# line_follower.net
KiCad netlist of a schematic drawn in EAGLE
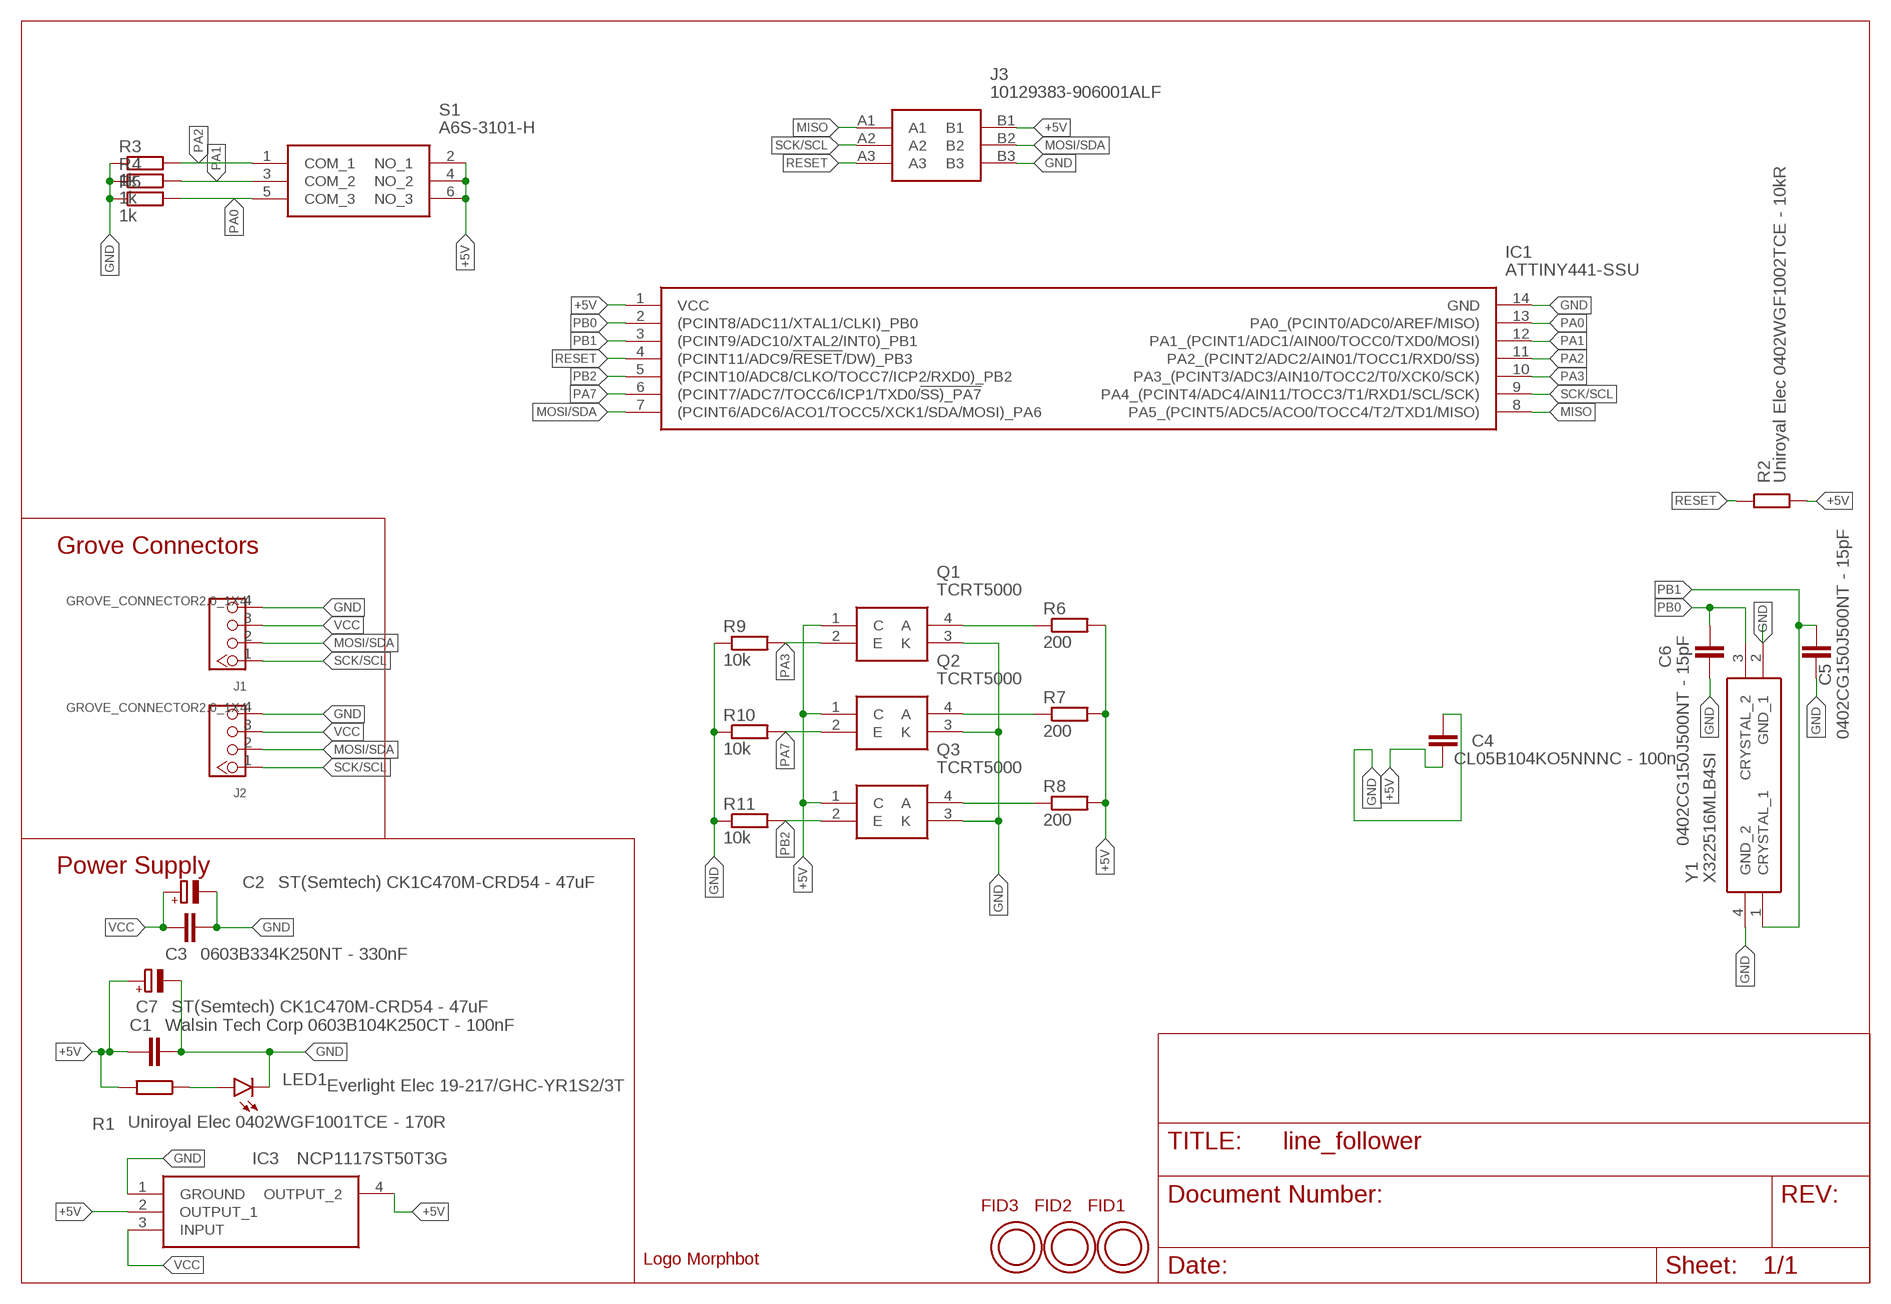
[diagram p0: schematic, sheet 1]

(export (version "E")
  (design (tool "Eeschema 10.0.6"))
  (components
    (comp (ref "C1")
      (value "Walsin Tech Corp 0603B104K250CT - 100nF")
      (footprint "eagle-import:C0603")
      (libsource (lib "eagle-import") (part "C-EUC0603"))
    )
    (comp (ref "C2")
      (value "ST(Semtech) CK1C470M-CRD54 - 47uF")
      (footprint "eagle-import:PANASONIC_C")
      (libsource (lib "eagle-import") (part "CPOL-EUC"))
    )
    (comp (ref "C3")
      (value "0603B334K250NT - 330nF")
      (footprint "eagle-import:C0603")
      (libsource (lib "eagle-import") (part "C-EUC0603"))
    )
    (comp (ref "C4")
      (value "CL05B104KO5NNNC - 100n")
      (footprint "eagle-import:C0402")
      (libsource (lib "eagle-import") (part "C-EUC0402"))
    )
    (comp (ref "C5")
      (value "0402CG150J500NT - 15pF")
      (footprint "eagle-import:C0402")
      (libsource (lib "eagle-import") (part "C-EUC0402"))
    )
    (comp (ref "C6")
      (value "0402CG150J500NT - 15pF")
      (footprint "eagle-import:C0402")
      (libsource (lib "eagle-import") (part "C-EUC0402"))
    )
    (comp (ref "C7")
      (value "ST(Semtech) CK1C470M-CRD54 - 47uF")
      (footprint "eagle-import:PANASONIC_C")
      (libsource (lib "eagle-import") (part "CPOL-EUC"))
    )
    (comp (ref "FID1")
      (value "OPEN-PNP-FIDUCIAL")
      (footprint "eagle-import:OPEN-PNP-FIDUCIAL")
      (libsource (lib "eagle-import") (part "OPEN-PNP-FIDUCIAL"))
    )
    (comp (ref "FID2")
      (value "OPEN-PNP-FIDUCIAL")
      (footprint "eagle-import:OPEN-PNP-FIDUCIAL")
      (libsource (lib "eagle-import") (part "OPEN-PNP-FIDUCIAL"))
    )
    (comp (ref "FID3")
      (value "OPEN-PNP-FIDUCIAL")
      (footprint "eagle-import:OPEN-PNP-FIDUCIAL")
      (libsource (lib "eagle-import") (part "OPEN-PNP-FIDUCIAL"))
    )
    (comp (ref "IC1")
      (value "ATTINY441-SSU")
      (footprint "eagle-import:SOIC127P600X175-14N")
      (fields (field (name "MOUSER_PART_NUMBER") "556-ATTINY441-SSU"))
      (libsource (lib "eagle-import") (part "ATTINY441-SSU"))
    )
    (comp (ref "IC3")
      (value "NCP1117ST50T3G")
      (footprint "eagle-import:SOT230P700X180-4N")
      (fields (field (name "MOUSER_PART_NUMBER") "863-NCP1117ST50T3G"))
      (libsource (lib "eagle-import") (part "NCP1117ST50T3G"))
    )
    (comp (ref "J1")
      (value "GROVE_CONNECTOR2.0_1X4")
      (footprint "eagle-import:2.0_1X4_STRAIGHT")
      (libsource (lib "eagle-import") (part "GROVE_CONNECTOR2.0_1X4"))
    )
    (comp (ref "J2")
      (value "GROVE_CONNECTOR2.0_1X4")
      (footprint "eagle-import:2.0_1X4_STRAIGHT")
      (libsource (lib "eagle-import") (part "GROVE_CONNECTOR2.0_1X4"))
    )
    (comp (ref "J3")
      (value "10129383-906001ALF")
      (footprint "eagle-import:10129383906001ALF")
      (fields (field (name "MOUSER_PART_NUMBER") "649-1012938390601ALF"))
      (libsource (lib "eagle-import") (part "10129383-906001ALF"))
    )
    (comp (ref "LED1")
      (value "Everlight Elec 19-217/GHC-YR1S2/3T")
      (footprint "eagle-import:CHIPLED_0603")
      (libsource (lib "eagle-import") (part "LEDCHIPLED_0603"))
    )
    (comp (ref "Q1")
      (value "TCRT5000")
      (footprint "eagle-import:TCRT5000")
      (fields (field (name "MOUSER_PART_NUMBER") "782-TCRT5000"))
      (libsource (lib "eagle-import") (part "TCRT5000"))
    )
    (comp (ref "Q2")
      (value "TCRT5000")
      (footprint "eagle-import:TCRT5000")
      (fields (field (name "MOUSER_PART_NUMBER") "782-TCRT5000"))
      (libsource (lib "eagle-import") (part "TCRT5000"))
    )
    (comp (ref "Q3")
      (value "TCRT5000")
      (footprint "eagle-import:TCRT5000")
      (fields (field (name "MOUSER_PART_NUMBER") "782-TCRT5000"))
      (libsource (lib "eagle-import") (part "TCRT5000"))
    )
    (comp (ref "R1")
      (value "Uniroyal Elec 0402WGF1001TCE - 170R")
      (footprint "eagle-import:R0402")
      (libsource (lib "eagle-import") (part "R-EU_R0402"))
    )
    (comp (ref "R2")
      (value "Uniroyal Elec 0402WGF1002TCE - 10kR")
      (footprint "eagle-import:R0402")
      (libsource (lib "eagle-import") (part "R-EU_R0402"))
    )
    (comp (ref "R3")
      (value "1k")
      (footprint "eagle-import:R0402")
      (libsource (lib "eagle-import") (part "R-EU_R0402"))
    )
    (comp (ref "R4")
      (value "1k")
      (footprint "eagle-import:R0402")
      (libsource (lib "eagle-import") (part "R-EU_R0402"))
    )
    (comp (ref "R5")
      (value "1k")
      (footprint "eagle-import:R0402")
      (libsource (lib "eagle-import") (part "R-EU_R0402"))
    )
    (comp (ref "R6")
      (value "200")
      (footprint "eagle-import:R0402")
      (libsource (lib "eagle-import") (part "R-EU_R0402"))
    )
    (comp (ref "R7")
      (value "200")
      (footprint "eagle-import:R0402")
      (libsource (lib "eagle-import") (part "R-EU_R0402"))
    )
    (comp (ref "R8")
      (value "200")
      (footprint "eagle-import:R0402")
      (libsource (lib "eagle-import") (part "R-EU_R0402"))
    )
    (comp (ref "R9")
      (value "10k")
      (footprint "eagle-import:R0402")
      (libsource (lib "eagle-import") (part "R-EU_R0402"))
    )
    (comp (ref "R10")
      (value "10k")
      (footprint "eagle-import:R0402")
      (libsource (lib "eagle-import") (part "R-EU_R0402"))
    )
    (comp (ref "R11")
      (value "10k")
      (footprint "eagle-import:R0402")
      (libsource (lib "eagle-import") (part "R-EU_R0402"))
    )
    (comp (ref "S1")
      (value "A6S-3101-H")
      (footprint "eagle-import:A6S3104H")
      (fields (field (name "MOUSER_PART_NUMBER") "653-A6S-3101-H"))
      (libsource (lib "eagle-import") (part "A6S-3101-H"))
    )
    (comp (ref "U$1")
      (value "LOGO_MORPHBOT5MM")
      (footprint "eagle-import:LOGO_MORPHBOT")
      (libsource (lib "eagle-import") (part "LOGO_MORPHBOT5MM"))
    )
    (comp (ref "Y1")
      (value "X322516MLB4SI")
      (footprint "eagle-import:X322516MLB4SI")
      (libsource (lib "eagle-import") (part "X322516MLB4SI"))
    )
  )
  (nets
    (net (code "1") (name "+5V") (class "Default")
      (node (ref "C1") (pin "1") (pinfunction "1_1") (pintype "passive"))
      (node (ref "C4") (pin "1") (pinfunction "1_1") (pintype "passive"))
      (node (ref "C7") (pin "+") (pinfunction "+_+") (pintype "passive"))
      (node (ref "IC1") (pin "1") (pinfunction "VCC_1") (pintype "bidirectional"))
      (node (ref "IC3") (pin "2") (pinfunction "OUTPUT_1_2") (pintype "bidirectional"))
      (node (ref "IC3") (pin "4") (pinfunction "OUTPUT_2_4") (pintype "bidirectional"))
      (node (ref "J3") (pin "B1") (pinfunction "B1_B1") (pintype "bidirectional"))
      (node (ref "Q1") (pin "1") (pinfunction "C_1") (pintype "bidirectional"))
      (node (ref "Q2") (pin "1") (pinfunction "C_1") (pintype "bidirectional"))
      (node (ref "Q3") (pin "1") (pinfunction "C_1") (pintype "bidirectional"))
      (node (ref "R1") (pin "2") (pinfunction "2_2") (pintype "passive"))
      (node (ref "R2") (pin "2") (pinfunction "2_2") (pintype "passive"))
      (node (ref "R6") (pin "2") (pinfunction "2_2") (pintype "passive"))
      (node (ref "R7") (pin "2") (pinfunction "2_2") (pintype "passive"))
      (node (ref "R8") (pin "2") (pinfunction "2_2") (pintype "passive"))
      (node (ref "S1") (pin "2") (pinfunction "NO_1_2") (pintype "bidirectional"))
      (node (ref "S1") (pin "4") (pinfunction "NO_2_4") (pintype "bidirectional"))
      (node (ref "S1") (pin "6") (pinfunction "NO_3_6") (pintype "bidirectional"))
    )
    (net (code "2") (name "GND") (class "Default")
      (node (ref "C1") (pin "2") (pinfunction "2_2") (pintype "passive"))
      (node (ref "C2") (pin "-") (pinfunction "-_-") (pintype "passive"))
      (node (ref "C3") (pin "1") (pinfunction "1_1") (pintype "passive"))
      (node (ref "C4") (pin "2") (pinfunction "2_2") (pintype "passive"))
      (node (ref "C5") (pin "1") (pinfunction "1_1") (pintype "passive"))
      (node (ref "C6") (pin "1") (pinfunction "1_1") (pintype "passive"))
      (node (ref "C7") (pin "-") (pinfunction "-_-") (pintype "passive"))
      (node (ref "IC1") (pin "14") (pinfunction "GND_14") (pintype "bidirectional"))
      (node (ref "IC3") (pin "1") (pinfunction "GROUND_1") (pintype "bidirectional"))
      (node (ref "J1") (pin "4") (pinfunction "4_4") (pintype "bidirectional"))
      (node (ref "J2") (pin "4") (pinfunction "4_4") (pintype "bidirectional"))
      (node (ref "J3") (pin "B3") (pinfunction "B3_B3") (pintype "bidirectional"))
      (node (ref "LED1") (pin "C") (pinfunction "C_C") (pintype "passive"))
      (node (ref "Q1") (pin "3") (pinfunction "K_3") (pintype "bidirectional"))
      (node (ref "Q2") (pin "3") (pinfunction "K_3") (pintype "bidirectional"))
      (node (ref "Q3") (pin "3") (pinfunction "K_3") (pintype "bidirectional"))
      (node (ref "R10") (pin "1") (pinfunction "1_1") (pintype "passive"))
      (node (ref "R11") (pin "1") (pinfunction "1_1") (pintype "passive"))
      (node (ref "R3") (pin "1") (pinfunction "1_1") (pintype "passive"))
      (node (ref "R4") (pin "1") (pinfunction "1_1") (pintype "passive"))
      (node (ref "R5") (pin "1") (pinfunction "1_1") (pintype "passive"))
      (node (ref "R9") (pin "1") (pinfunction "1_1") (pintype "passive"))
      (node (ref "Y1") (pin "2") (pinfunction "GND_1_2") (pintype "bidirectional"))
      (node (ref "Y1") (pin "4") (pinfunction "GND_2_4") (pintype "bidirectional"))
    )
    (net (code "3") (name "MISO") (class "Default")
      (node (ref "IC1") (pin "8") (pinfunction "PA5_(PCINT5/ADC5/ACO0/TOCC4/T2/TXD1/MISO)_8") (pintype "bidirectional"))
      (node (ref "J3") (pin "A1") (pinfunction "A1_A1") (pintype "bidirectional"))
    )
    (net (code "4") (name "MOSI{slash}SDA") (class "Default")
      (node (ref "IC1") (pin "7") (pinfunction "(PCINT6/ADC6/ACO1/TOCC5/XCK1/SDA/MOSI)_PA6_7") (pintype "bidirectional"))
      (node (ref "J1") (pin "2") (pinfunction "2_2") (pintype "bidirectional"))
      (node (ref "J2") (pin "2") (pinfunction "2_2") (pintype "bidirectional"))
      (node (ref "J3") (pin "B2") (pinfunction "B2_B2") (pintype "bidirectional"))
    )
    (net (code "5") (name "Net-(LED1-PadA)") (class "Default")
      (node (ref "LED1") (pin "A") (pinfunction "A_A") (pintype "passive"))
      (node (ref "R1") (pin "1") (pinfunction "1_1") (pintype "passive"))
    )
    (net (code "6") (name "Net-(Q1-A)") (class "Default")
      (node (ref "Q1") (pin "4") (pinfunction "A_4") (pintype "bidirectional"))
      (node (ref "R6") (pin "1") (pinfunction "1_1") (pintype "passive"))
    )
    (net (code "7") (name "Net-(Q2-A)") (class "Default")
      (node (ref "Q2") (pin "4") (pinfunction "A_4") (pintype "bidirectional"))
      (node (ref "R7") (pin "1") (pinfunction "1_1") (pintype "passive"))
    )
    (net (code "8") (name "Net-(Q3-A)") (class "Default")
      (node (ref "Q3") (pin "4") (pinfunction "A_4") (pintype "bidirectional"))
      (node (ref "R8") (pin "1") (pinfunction "1_1") (pintype "passive"))
    )
    (net (code "9") (name "PA0") (class "Default")
      (node (ref "IC1") (pin "13") (pinfunction "PA0_(PCINT0/ADC0/AREF/MISO)_13") (pintype "bidirectional"))
      (node (ref "R5") (pin "2") (pinfunction "2_2") (pintype "passive"))
      (node (ref "S1") (pin "5") (pinfunction "COM_3_5") (pintype "bidirectional"))
    )
    (net (code "10") (name "PA1") (class "Default")
      (node (ref "IC1") (pin "12") (pinfunction "PA1_(PCINT1/ADC1/AIN00/TOCC0/TXD0/MOSI)_12") (pintype "bidirectional"))
      (node (ref "R4") (pin "2") (pinfunction "2_2") (pintype "passive"))
      (node (ref "S1") (pin "3") (pinfunction "COM_2_3") (pintype "bidirectional"))
    )
    (net (code "11") (name "PA2") (class "Default")
      (node (ref "IC1") (pin "11") (pinfunction "PA2_(PCINT2/ADC2/AIN01/TOCC1/RXD0/SS)_11") (pintype "bidirectional"))
      (node (ref "R3") (pin "2") (pinfunction "2_2") (pintype "passive"))
      (node (ref "S1") (pin "1") (pinfunction "COM_1_1") (pintype "bidirectional"))
    )
    (net (code "12") (name "PA3") (class "Default")
      (node (ref "IC1") (pin "10") (pinfunction "PA3_(PCINT3/ADC3/AIN10/TOCC2/T0/XCK0/SCK)_10") (pintype "bidirectional"))
      (node (ref "Q1") (pin "2") (pinfunction "E_2") (pintype "bidirectional"))
      (node (ref "R9") (pin "2") (pinfunction "2_2") (pintype "passive"))
    )
    (net (code "13") (name "PA7") (class "Default")
      (node (ref "IC1") (pin "6") (pinfunction "(PCINT7/ADC7/TOCC6/ICP1/TXD0/~{SS})_PA7_6") (pintype "bidirectional"))
      (node (ref "Q2") (pin "2") (pinfunction "E_2") (pintype "bidirectional"))
      (node (ref "R10") (pin "2") (pinfunction "2_2") (pintype "passive"))
    )
    (net (code "14") (name "PB0") (class "Default")
      (node (ref "C6") (pin "2") (pinfunction "2_2") (pintype "passive"))
      (node (ref "IC1") (pin "2") (pinfunction "(PCINT8/ADC11/XTAL1/CLKI)_PB0_2") (pintype "bidirectional"))
      (node (ref "Y1") (pin "3") (pinfunction "CRYSTAL_2_3") (pintype "bidirectional"))
    )
    (net (code "15") (name "PB1") (class "Default")
      (node (ref "C5") (pin "2") (pinfunction "2_2") (pintype "passive"))
      (node (ref "IC1") (pin "3") (pinfunction "(PCINT9/ADC10/XTAL2/INT0)_PB1_3") (pintype "bidirectional"))
      (node (ref "Y1") (pin "1") (pinfunction "CRYSTAL_1_1") (pintype "bidirectional"))
    )
    (net (code "16") (name "PB2") (class "Default")
      (node (ref "IC1") (pin "5") (pinfunction "(PCINT10/ADC8/CLKO/TOCC7/ICP2/RXD0)_PB2_5") (pintype "bidirectional"))
      (node (ref "Q3") (pin "2") (pinfunction "E_2") (pintype "bidirectional"))
      (node (ref "R11") (pin "2") (pinfunction "2_2") (pintype "passive"))
    )
    (net (code "17") (name "RESET") (class "Default")
      (node (ref "IC1") (pin "4") (pinfunction "(PCINT11/ADC9/~{RESET}/DW)_PB3_4") (pintype "bidirectional"))
      (node (ref "J3") (pin "A3") (pinfunction "A3_A3") (pintype "bidirectional"))
      (node (ref "R2") (pin "1") (pinfunction "1_1") (pintype "passive"))
    )
    (net (code "18") (name "SCK{slash}SCL") (class "Default")
      (node (ref "IC1") (pin "9") (pinfunction "PA4_(PCINT4/ADC4/AIN11/TOCC3/T1/RXD1/SCL/SCK)_9") (pintype "bidirectional"))
      (node (ref "J1") (pin "1") (pinfunction "1_1") (pintype "bidirectional"))
      (node (ref "J2") (pin "1") (pinfunction "1_1") (pintype "bidirectional"))
      (node (ref "J3") (pin "A2") (pinfunction "A2_A2") (pintype "bidirectional"))
    )
    (net (code "19") (name "VCC") (class "Default")
      (node (ref "C2") (pin "+") (pinfunction "+_+") (pintype "passive"))
      (node (ref "C3") (pin "2") (pinfunction "2_2") (pintype "passive"))
      (node (ref "IC3") (pin "3") (pinfunction "INPUT_3") (pintype "bidirectional"))
      (node (ref "J1") (pin "3") (pinfunction "3_3") (pintype "bidirectional"))
      (node (ref "J2") (pin "3") (pinfunction "3_3") (pintype "bidirectional"))
    )
  )
)
